# blue-led-2.net
KiCad netlist of a schematic drawn in EAGLE
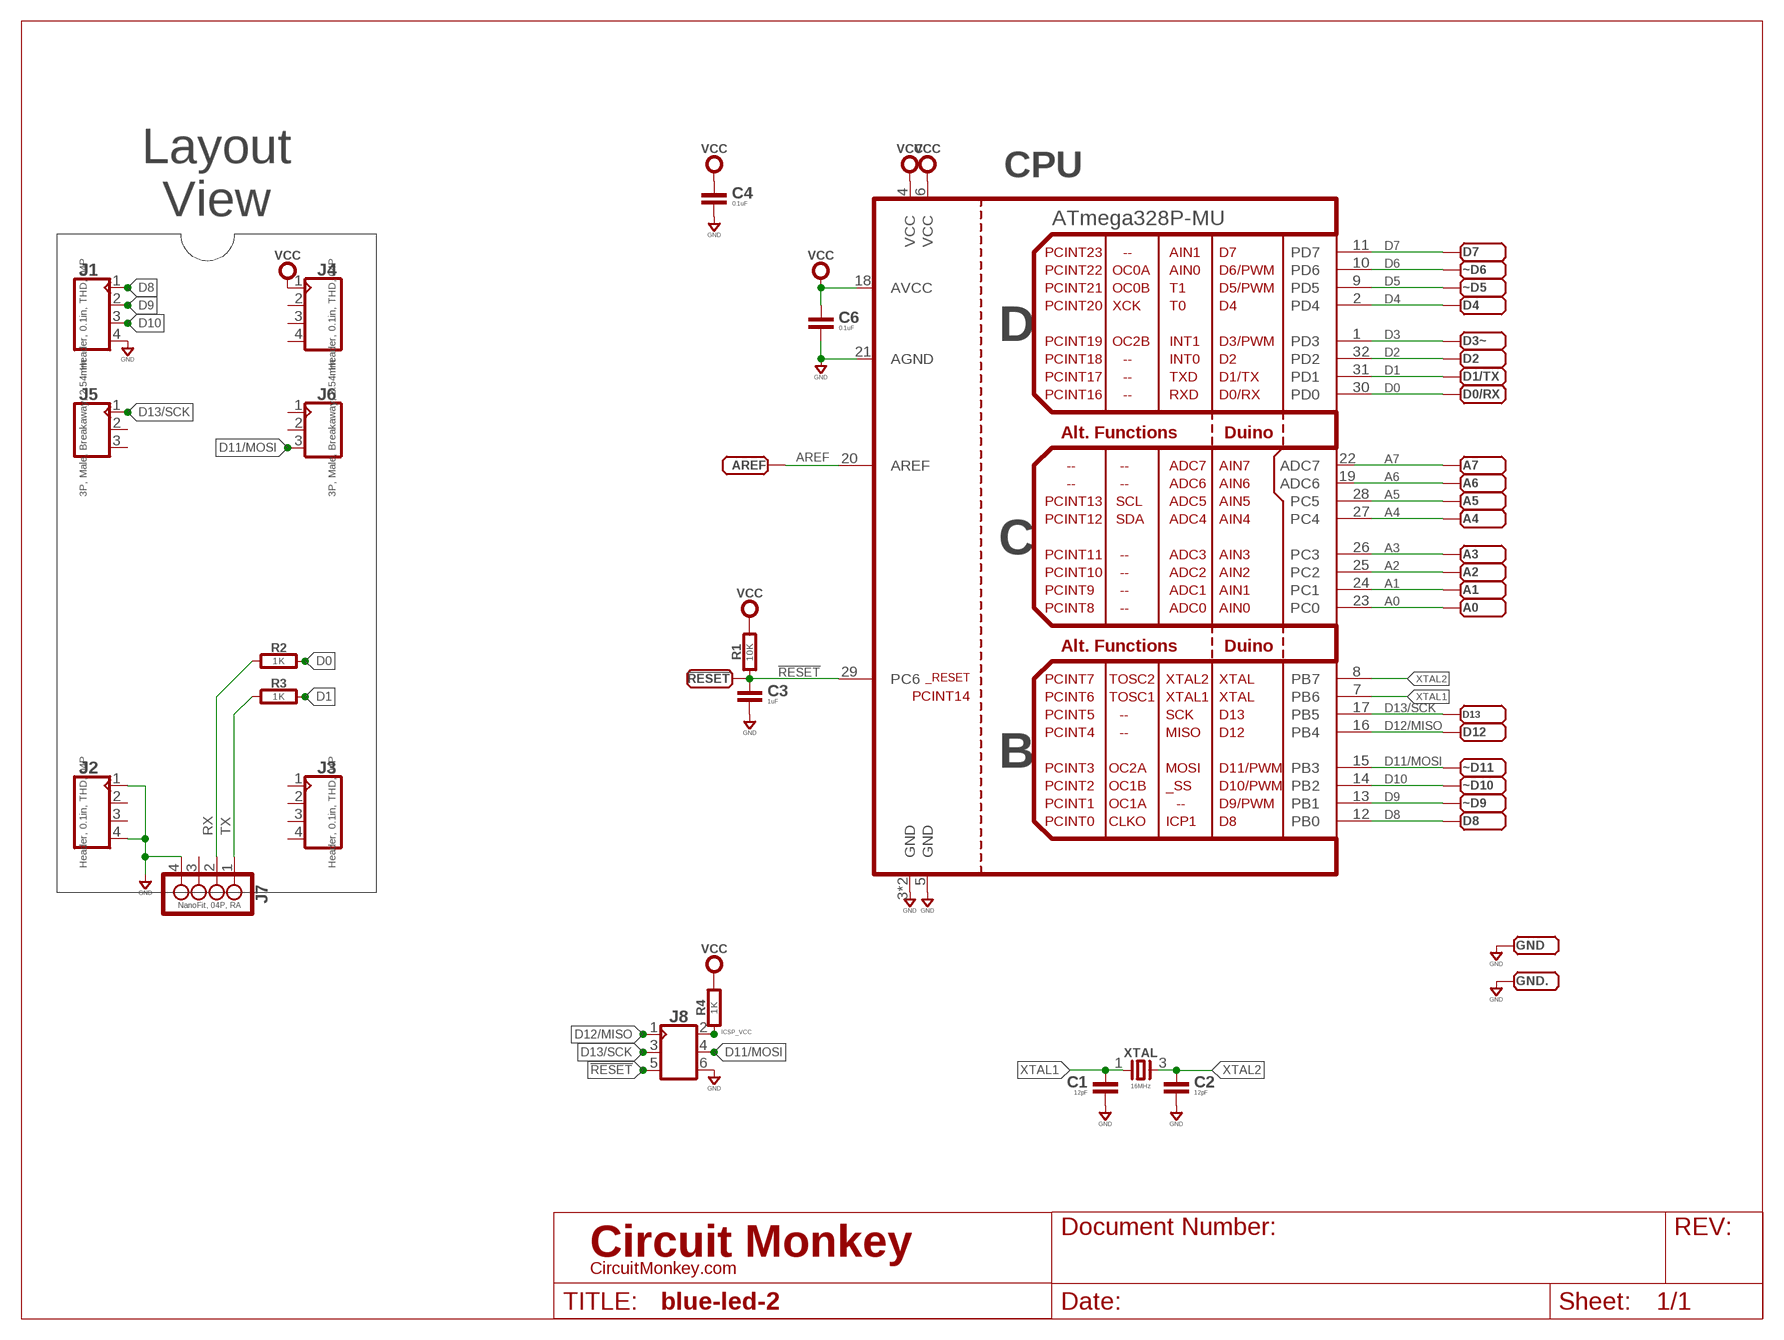
[diagram p0: schematic, sheet 1]

(export (version "E")
  (design (tool "Eeschema 10.0.6"))
  (components
    (comp (ref "!RESET")
      (value "PADSMD-050X050")
      (footprint "eagle-import:SMD-050X050")
      (libsource (lib "eagle-import") (part "PADSMD-050X050"))
    )
    (comp (ref "A0")
      (value "PADSMD-050X050")
      (footprint "eagle-import:SMD-050X050")
      (libsource (lib "eagle-import") (part "PADSMD-050X050"))
    )
    (comp (ref "A1")
      (value "PADSMD-050X050")
      (footprint "eagle-import:SMD-050X050")
      (libsource (lib "eagle-import") (part "PADSMD-050X050"))
    )
    (comp (ref "A2")
      (value "PADSMD-050X050")
      (footprint "eagle-import:SMD-050X050")
      (libsource (lib "eagle-import") (part "PADSMD-050X050"))
    )
    (comp (ref "A3")
      (value "PADSMD-050X050")
      (footprint "eagle-import:SMD-050X050")
      (libsource (lib "eagle-import") (part "PADSMD-050X050"))
    )
    (comp (ref "A4")
      (value "PADSMD-050X050")
      (footprint "eagle-import:SMD-050X050")
      (libsource (lib "eagle-import") (part "PADSMD-050X050"))
    )
    (comp (ref "A5")
      (value "PADSMD-050X050")
      (footprint "eagle-import:SMD-050X050")
      (libsource (lib "eagle-import") (part "PADSMD-050X050"))
    )
    (comp (ref "A6")
      (value "PADSMD-050X050")
      (footprint "eagle-import:SMD-050X050")
      (libsource (lib "eagle-import") (part "PADSMD-050X050"))
    )
    (comp (ref "A7")
      (value "PADSMD-050X050")
      (footprint "eagle-import:SMD-050X050")
      (libsource (lib "eagle-import") (part "PADSMD-050X050"))
    )
    (comp (ref "AREF")
      (value "PADSMD-050X050")
      (footprint "eagle-import:SMD-050X050")
      (libsource (lib "eagle-import") (part "PADSMD-050X050"))
    )
    (comp (ref "C1")
      (value "12pF")
      (footprint "eagle-import:0603-CAP")
      (libsource (lib "eagle-import") (part "CAPACITOR0603"))
    )
    (comp (ref "C2")
      (value "12pF")
      (footprint "eagle-import:0603-CAP")
      (libsource (lib "eagle-import") (part "CAPACITOR0603"))
    )
    (comp (ref "C3")
      (value "1uF")
      (footprint "eagle-import:0603-CAP")
      (libsource (lib "eagle-import") (part "CAPACITOR0603"))
    )
    (comp (ref "C4")
      (value "0.1uF")
      (footprint "eagle-import:0603-CAP")
      (libsource (lib "eagle-import") (part "CAPACITOR0603"))
    )
    (comp (ref "C6")
      (value "0.1uF")
      (footprint "eagle-import:0603-CAP")
      (libsource (lib "eagle-import") (part "CAPACITOR0603"))
    )
    (comp (ref "CPU")
      (value "ATmega328P-MU")
      (footprint "eagle-import:MLF32")
      (fields (field (name "MFR") "Atmel") (field (name "MPN") "atmega328p-mu"))
      (libsource (lib "eagle-import") (part "ATMEGA328MU"))
    )
    (comp (ref "D0/RX")
      (value "PADSMD-050X050")
      (footprint "eagle-import:SMD-050X050")
      (libsource (lib "eagle-import") (part "PADSMD-050X050"))
    )
    (comp (ref "D1/TX")
      (value "PADSMD-050X050")
      (footprint "eagle-import:SMD-050X050")
      (libsource (lib "eagle-import") (part "PADSMD-050X050"))
    )
    (comp (ref "D2")
      (value "PADSMD-050X050")
      (footprint "eagle-import:SMD-050X050")
      (libsource (lib "eagle-import") (part "PADSMD-050X050"))
    )
    (comp (ref "D3~")
      (value "PADSMD-050X050")
      (footprint "eagle-import:SMD-050X050")
      (libsource (lib "eagle-import") (part "PADSMD-050X050"))
    )
    (comp (ref "D4")
      (value "PADSMD-050X050")
      (footprint "eagle-import:SMD-050X050")
      (libsource (lib "eagle-import") (part "PADSMD-050X050"))
    )
    (comp (ref "D7")
      (value "PADSMD-050X050")
      (footprint "eagle-import:SMD-050X050")
      (libsource (lib "eagle-import") (part "PADSMD-050X050"))
    )
    (comp (ref "D8")
      (value "PADSMD-050X050")
      (footprint "eagle-import:SMD-050X050")
      (libsource (lib "eagle-import") (part "PADSMD-050X050"))
    )
    (comp (ref "D12")
      (value "PADSMD-050X050")
      (footprint "eagle-import:SMD-050X050")
      (libsource (lib "eagle-import") (part "PADSMD-050X050"))
    )
    (comp (ref "D13")
      (value "PADSMD-050X050")
      (footprint "eagle-import:SMD-050X050")
      (libsource (lib "eagle-import") (part "PADSMD-050X050"))
    )
    (comp (ref "GND")
      (value "PADSMD-050X050")
      (footprint "eagle-import:SMD-050X050")
      (libsource (lib "eagle-import") (part "PADSMD-050X050"))
    )
    (comp (ref "GND.")
      (value "PADSMD-050X050")
      (footprint "eagle-import:SMD-050X050")
      (libsource (lib "eagle-import") (part "PADSMD-050X050"))
    )
    (comp (ref "J1")
      (value "Header, 0.1in, THD, 04P")
      (footprint "eagle-import:MA04X1-VT-THD")
      (fields (field (name "MFR") "Molex") (field (name "MPN") "022284043"))
      (libsource (lib "eagle-import") (part "CON_04X1-THD-VT"))
    )
    (comp (ref "J2")
      (value "Header, 0.1in, THD, 04P")
      (footprint "eagle-import:MA04X1-VT-THD")
      (fields (field (name "MFR") "Molex") (field (name "MPN") "022284043"))
      (libsource (lib "eagle-import") (part "CON_04X1-THD-VT"))
    )
    (comp (ref "J3")
      (value "Header, 0.1in, THD, 04P")
      (footprint "eagle-import:MA04X1-VT-THD")
      (fields (field (name "MFR") "Molex") (field (name "MPN") "022284043"))
      (libsource (lib "eagle-import") (part "CON_04X1-THD-VT"))
    )
    (comp (ref "J4")
      (value "Header, 0.1in, THD, 04P")
      (footprint "eagle-import:MA04X1-VT-THD")
      (fields (field (name "MFR") "Molex") (field (name "MPN") "022284043"))
      (libsource (lib "eagle-import") (part "CON_04X1-THD-VT"))
    )
    (comp (ref "J5")
      (value "3P, Male, Breakaway, 2.54mm")
      (footprint "eagle-import:MA03X1-VT-THD")
      (libsource (lib "eagle-import") (part "CON_03X1-2.54MM-THD-VT"))
    )
    (comp (ref "J6")
      (value "3P, Male, Breakaway, 2.54mm")
      (footprint "eagle-import:MA03X1-VT-THD")
      (libsource (lib "eagle-import") (part "CON_03X1-2.54MM-THD-VT"))
    )
    (comp (ref "J7")
      (value "NanoFit, 04P, RA")
      (footprint "eagle-import:MOLEX-105313-XX04")
      (fields (field (name "MFR") "Molex") (field (name "MPN") "105313-XX04"))
      (libsource (lib "eagle-import") (part "NANOFIT-04P-SR-RA"))
    )
    (comp (ref "J8")
      (value "CON_03X2-VT_SMD")
      (footprint "eagle-import:MA03X2-VT-SMD")
      (libsource (lib "eagle-import") (part "CON_03X2-VT_SMD"))
    )
    (comp (ref "R1")
      (value "10K")
      (footprint "eagle-import:0603-RES")
      (libsource (lib "eagle-import") (part "RESISTOR0603"))
    )
    (comp (ref "R2")
      (value "1K")
      (footprint "eagle-import:0603-RES")
      (libsource (lib "eagle-import") (part "RESISTOR0603"))
    )
    (comp (ref "R3")
      (value "1K")
      (footprint "eagle-import:0603-RES")
      (libsource (lib "eagle-import") (part "RESISTOR0603"))
    )
    (comp (ref "R4")
      (value "1K")
      (footprint "eagle-import:0603-RES")
      (libsource (lib "eagle-import") (part "RESISTOR0603"))
    )
    (comp (ref "XTAL")
      (value "16MHz")
      (footprint "eagle-import:32X25")
      (fields (field (name "MFR") "Epson") (field (name "MPN") "FA-238 16.0000MB-K3"))
      (libsource (lib "eagle-import") (part "2P3.2X2.5"))
    )
    (comp (ref "~D5")
      (value "PADSMD-050X050")
      (footprint "eagle-import:SMD-050X050")
      (libsource (lib "eagle-import") (part "PADSMD-050X050"))
    )
    (comp (ref "~D6")
      (value "PADSMD-050X050")
      (footprint "eagle-import:SMD-050X050")
      (libsource (lib "eagle-import") (part "PADSMD-050X050"))
    )
    (comp (ref "~D9")
      (value "PADSMD-050X050")
      (footprint "eagle-import:SMD-050X050")
      (libsource (lib "eagle-import") (part "PADSMD-050X050"))
    )
    (comp (ref "~D10")
      (value "PADSMD-050X050")
      (footprint "eagle-import:SMD-050X050")
      (libsource (lib "eagle-import") (part "PADSMD-050X050"))
    )
    (comp (ref "~D11")
      (value "PADSMD-050X050")
      (footprint "eagle-import:SMD-050X050")
      (libsource (lib "eagle-import") (part "PADSMD-050X050"))
    )
  )
  (nets
    (net (code "1") (name "/A0") (class "Default")
      (node (ref "A0") (pin "1") (pinfunction "PAD_1") (pintype "bidirectional"))
      (node (ref "CPU") (pin "23") (pinfunction "PC0_23") (pintype "bidirectional"))
    )
    (net (code "2") (name "/A1") (class "Default")
      (node (ref "A1") (pin "1") (pinfunction "PAD_1") (pintype "bidirectional"))
      (node (ref "CPU") (pin "24") (pinfunction "PC1_24") (pintype "bidirectional"))
    )
    (net (code "3") (name "/A2") (class "Default")
      (node (ref "A2") (pin "1") (pinfunction "PAD_1") (pintype "bidirectional"))
      (node (ref "CPU") (pin "25") (pinfunction "PC2_25") (pintype "bidirectional"))
    )
    (net (code "4") (name "/A3") (class "Default")
      (node (ref "A3") (pin "1") (pinfunction "PAD_1") (pintype "bidirectional"))
      (node (ref "CPU") (pin "26") (pinfunction "PC3_26") (pintype "bidirectional"))
    )
    (net (code "5") (name "/A4") (class "Default")
      (node (ref "A4") (pin "1") (pinfunction "PAD_1") (pintype "bidirectional"))
      (node (ref "CPU") (pin "27") (pinfunction "PC4_27") (pintype "bidirectional"))
    )
    (net (code "6") (name "/A5") (class "Default")
      (node (ref "A5") (pin "1") (pinfunction "PAD_1") (pintype "bidirectional"))
      (node (ref "CPU") (pin "28") (pinfunction "PC5_28") (pintype "bidirectional"))
    )
    (net (code "7") (name "/A6") (class "Default")
      (node (ref "A6") (pin "1") (pinfunction "PAD_1") (pintype "bidirectional"))
      (node (ref "CPU") (pin "19") (pinfunction "ADC6_19") (pintype "bidirectional"))
    )
    (net (code "8") (name "/A7") (class "Default")
      (node (ref "A7") (pin "1") (pinfunction "PAD_1") (pintype "bidirectional"))
      (node (ref "CPU") (pin "22") (pinfunction "ADC7_22") (pintype "bidirectional"))
    )
    (net (code "9") (name "/AREF") (class "Default")
      (node (ref "AREF") (pin "1") (pinfunction "PAD_1") (pintype "bidirectional"))
      (node (ref "CPU") (pin "20") (pinfunction "AREF_20") (pintype "input"))
    )
    (net (code "10") (name "/D2") (class "Default")
      (node (ref "CPU") (pin "32") (pinfunction "PD2_32") (pintype "bidirectional"))
      (node (ref "D2") (pin "1") (pinfunction "PAD_1") (pintype "bidirectional"))
    )
    (net (code "11") (name "/D3") (class "Default")
      (node (ref "CPU") (pin "1") (pinfunction "PD3_1") (pintype "bidirectional"))
      (node (ref "D3~") (pin "1") (pinfunction "PAD_1") (pintype "bidirectional"))
    )
    (net (code "12") (name "/D4") (class "Default")
      (node (ref "CPU") (pin "2") (pinfunction "PD4_2") (pintype "bidirectional"))
      (node (ref "D4") (pin "1") (pinfunction "PAD_1") (pintype "bidirectional"))
    )
    (net (code "13") (name "/D5") (class "Default")
      (node (ref "CPU") (pin "9") (pinfunction "PD5_9") (pintype "bidirectional"))
      (node (ref "~D5") (pin "1") (pinfunction "PAD_1") (pintype "bidirectional"))
    )
    (net (code "14") (name "/D6") (class "Default")
      (node (ref "CPU") (pin "10") (pinfunction "PD6_10") (pintype "bidirectional"))
      (node (ref "~D6") (pin "1") (pinfunction "PAD_1") (pintype "bidirectional"))
    )
    (net (code "15") (name "/D7") (class "Default")
      (node (ref "CPU") (pin "11") (pinfunction "PD7_11") (pintype "bidirectional"))
      (node (ref "D7") (pin "1") (pinfunction "PAD_1") (pintype "bidirectional"))
    )
    (net (code "17") (name "/ICSP_VCC") (class "Default")
      (node (ref "J8") (pin "2") (pinfunction "2_2") (pintype "passive"))
      (node (ref "R4") (pin "1") (pinfunction "1_1") (pintype "passive"))
    )
    (net (code "18") (name "/RX") (class "Default")
      (node (ref "J7") (pin "2") (pinfunction "2_2") (pintype "bidirectional"))
      (node (ref "R2") (pin "1") (pinfunction "1_1") (pintype "passive"))
    )
    (net (code "19") (name "/TX") (class "Default")
      (node (ref "J7") (pin "1") (pinfunction "1_1") (pintype "bidirectional"))
      (node (ref "R3") (pin "1") (pinfunction "1_1") (pintype "passive"))
    )
    (net (code "20") (name "/~{RESET}") (class "Default")
      (node (ref "!RESET") (pin "1") (pinfunction "PAD_1") (pintype "bidirectional"))
      (node (ref "C3") (pin "1") (pinfunction "1_1") (pintype "passive"))
      (node (ref "CPU") (pin "29") (pinfunction "PC6_29") (pintype "bidirectional"))
      (node (ref "J8") (pin "5") (pinfunction "5_5") (pintype "passive"))
      (node (ref "R1") (pin "1") (pinfunction "1_1") (pintype "passive"))
    )
    (net (code "21") (name "D0") (class "Default")
      (node (ref "CPU") (pin "30") (pinfunction "PD0_30") (pintype "bidirectional"))
      (node (ref "D0/RX") (pin "1") (pinfunction "PAD_1") (pintype "bidirectional"))
      (node (ref "R2") (pin "2") (pinfunction "2_2") (pintype "passive"))
    )
    (net (code "22") (name "D1") (class "Default")
      (node (ref "CPU") (pin "31") (pinfunction "PD1_31") (pintype "bidirectional"))
      (node (ref "D1/TX") (pin "1") (pinfunction "PAD_1") (pintype "bidirectional"))
      (node (ref "R3") (pin "2") (pinfunction "2_2") (pintype "passive"))
    )
    (net (code "23") (name "D8") (class "Default")
      (node (ref "CPU") (pin "12") (pinfunction "PB0_12") (pintype "bidirectional"))
      (node (ref "D8") (pin "1") (pinfunction "PAD_1") (pintype "bidirectional"))
      (node (ref "J1") (pin "1") (pinfunction "1_1") (pintype "passive"))
    )
    (net (code "24") (name "D9") (class "Default")
      (node (ref "CPU") (pin "13") (pinfunction "PB1_13") (pintype "bidirectional"))
      (node (ref "J1") (pin "2") (pinfunction "2_2") (pintype "passive"))
      (node (ref "~D9") (pin "1") (pinfunction "PAD_1") (pintype "bidirectional"))
    )
    (net (code "25") (name "D10") (class "Default")
      (node (ref "CPU") (pin "14") (pinfunction "PB2_14") (pintype "bidirectional"))
      (node (ref "J1") (pin "3") (pinfunction "3_3") (pintype "passive"))
      (node (ref "~D10") (pin "1") (pinfunction "PAD_1") (pintype "bidirectional"))
    )
    (net (code "26") (name "D11{slash}MOSI") (class "Default")
      (node (ref "CPU") (pin "15") (pinfunction "PB3_15") (pintype "bidirectional"))
      (node (ref "J6") (pin "3") (pinfunction "3_3") (pintype "passive"))
      (node (ref "J8") (pin "4") (pinfunction "4_4") (pintype "passive"))
      (node (ref "~D11") (pin "1") (pinfunction "PAD_1") (pintype "bidirectional"))
    )
    (net (code "27") (name "D12{slash}MISO") (class "Default")
      (node (ref "CPU") (pin "16") (pinfunction "PB4_16") (pintype "bidirectional"))
      (node (ref "D12") (pin "1") (pinfunction "PAD_1") (pintype "bidirectional"))
      (node (ref "J8") (pin "1") (pinfunction "1_1") (pintype "passive"))
    )
    (net (code "28") (name "D13{slash}SCK") (class "Default")
      (node (ref "CPU") (pin "17") (pinfunction "PB5_17") (pintype "bidirectional"))
      (node (ref "D13") (pin "1") (pinfunction "PAD_1") (pintype "bidirectional"))
      (node (ref "J5") (pin "1") (pinfunction "1_1") (pintype "passive"))
      (node (ref "J8") (pin "3") (pinfunction "3_3") (pintype "passive"))
    )
    (net (code "29") (name "GND") (class "Default")
      (node (ref "C1") (pin "2") (pinfunction "2_2") (pintype "passive"))
      (node (ref "C2") (pin "2") (pinfunction "2_2") (pintype "passive"))
      (node (ref "C3") (pin "2") (pinfunction "2_2") (pintype "passive"))
      (node (ref "C4") (pin "2") (pinfunction "2_2") (pintype "passive"))
      (node (ref "C6") (pin "2") (pinfunction "2_2") (pintype "passive"))
      (node (ref "CPU") (pin "21") (pinfunction "AGND_21") (pintype "power_in"))
      (node (ref "CPU") (pin "3") (pinfunction "GND_3") (pintype "power_in"))
      (node (ref "CPU") (pin "5") (pinfunction "GND_5") (pintype "power_in"))
      (node (ref "CPU") (pin "PAD") (pinfunction "GND_PAD") (pintype "power_in"))
      (node (ref "GND") (pin "1") (pinfunction "PAD_1") (pintype "bidirectional"))
      (node (ref "GND.") (pin "1") (pinfunction "PAD_1") (pintype "bidirectional"))
      (node (ref "J1") (pin "4") (pinfunction "4_4") (pintype "passive"))
      (node (ref "J2") (pin "1") (pinfunction "1_1") (pintype "passive"))
      (node (ref "J2") (pin "4") (pinfunction "4_4") (pintype "passive"))
      (node (ref "J7") (pin "4") (pinfunction "4_4") (pintype "bidirectional"))
      (node (ref "J8") (pin "6") (pinfunction "6_6") (pintype "passive"))
    )
    (net (code "30") (name "VCC") (class "Default")
      (node (ref "C4") (pin "1") (pinfunction "1_1") (pintype "passive"))
      (node (ref "C6") (pin "1") (pinfunction "1_1") (pintype "passive"))
      (node (ref "CPU") (pin "18") (pinfunction "AVCC_18") (pintype "power_in"))
      (node (ref "CPU") (pin "4") (pinfunction "VCC_4") (pintype "power_in"))
      (node (ref "CPU") (pin "6") (pinfunction "VCC_6") (pintype "power_in"))
      (node (ref "J4") (pin "1") (pinfunction "1_1") (pintype "passive"))
      (node (ref "R1") (pin "2") (pinfunction "2_2") (pintype "passive"))
      (node (ref "R4") (pin "2") (pinfunction "2_2") (pintype "passive"))
    )
    (net (code "31") (name "XTAL1") (class "Default")
      (node (ref "C1") (pin "1") (pinfunction "1_1") (pintype "passive"))
      (node (ref "CPU") (pin "7") (pinfunction "PB6_7") (pintype "bidirectional"))
      (node (ref "XTAL") (pin "1") (pinfunction "P$1_1") (pintype "passive"))
    )
    (net (code "32") (name "XTAL2") (class "Default")
      (node (ref "C2") (pin "1") (pinfunction "1_1") (pintype "passive"))
      (node (ref "CPU") (pin "8") (pinfunction "PB7_8") (pintype "bidirectional"))
      (node (ref "XTAL") (pin "3") (pinfunction "P$2_3") (pintype "passive"))
    )
    (net (code "33") (name "unconnected-(J2-Pad2)") (class "Default")
      (node (ref "J2") (pin "2") (pinfunction "2_2") (pintype "passive"))
    )
    (net (code "34") (name "unconnected-(J2-Pad3)") (class "Default")
      (node (ref "J2") (pin "3") (pinfunction "3_3") (pintype "passive"))
    )
    (net (code "35") (name "unconnected-(J3-Pad1)") (class "Default")
      (node (ref "J3") (pin "1") (pinfunction "1_1") (pintype "passive"))
    )
    (net (code "36") (name "unconnected-(J3-Pad2)") (class "Default")
      (node (ref "J3") (pin "2") (pinfunction "2_2") (pintype "passive"))
    )
    (net (code "37") (name "unconnected-(J3-Pad3)") (class "Default")
      (node (ref "J3") (pin "3") (pinfunction "3_3") (pintype "passive"))
    )
    (net (code "38") (name "unconnected-(J3-Pad4)") (class "Default")
      (node (ref "J3") (pin "4") (pinfunction "4_4") (pintype "passive"))
    )
    (net (code "39") (name "unconnected-(J4-Pad2)") (class "Default")
      (node (ref "J4") (pin "2") (pinfunction "2_2") (pintype "passive"))
    )
    (net (code "40") (name "unconnected-(J4-Pad3)") (class "Default")
      (node (ref "J4") (pin "3") (pinfunction "3_3") (pintype "passive"))
    )
    (net (code "41") (name "unconnected-(J4-Pad4)") (class "Default")
      (node (ref "J4") (pin "4") (pinfunction "4_4") (pintype "passive"))
    )
    (net (code "42") (name "unconnected-(J5-Pad2)") (class "Default")
      (node (ref "J5") (pin "2") (pinfunction "2_2") (pintype "passive"))
    )
    (net (code "43") (name "unconnected-(J5-Pad3)") (class "Default")
      (node (ref "J5") (pin "3") (pinfunction "3_3") (pintype "passive"))
    )
    (net (code "44") (name "unconnected-(J6-Pad1)") (class "Default")
      (node (ref "J6") (pin "1") (pinfunction "1_1") (pintype "passive"))
    )
    (net (code "45") (name "unconnected-(J6-Pad2)") (class "Default")
      (node (ref "J6") (pin "2") (pinfunction "2_2") (pintype "passive"))
    )
    (net (code "46") (name "unconnected-(J7-Pad3)") (class "Default")
      (node (ref "J7") (pin "3") (pinfunction "3_3") (pintype "bidirectional"))
    )
  )
)
